# Boris_IO_4.net
KiCad netlist of a schematic drawn in Altium Designer
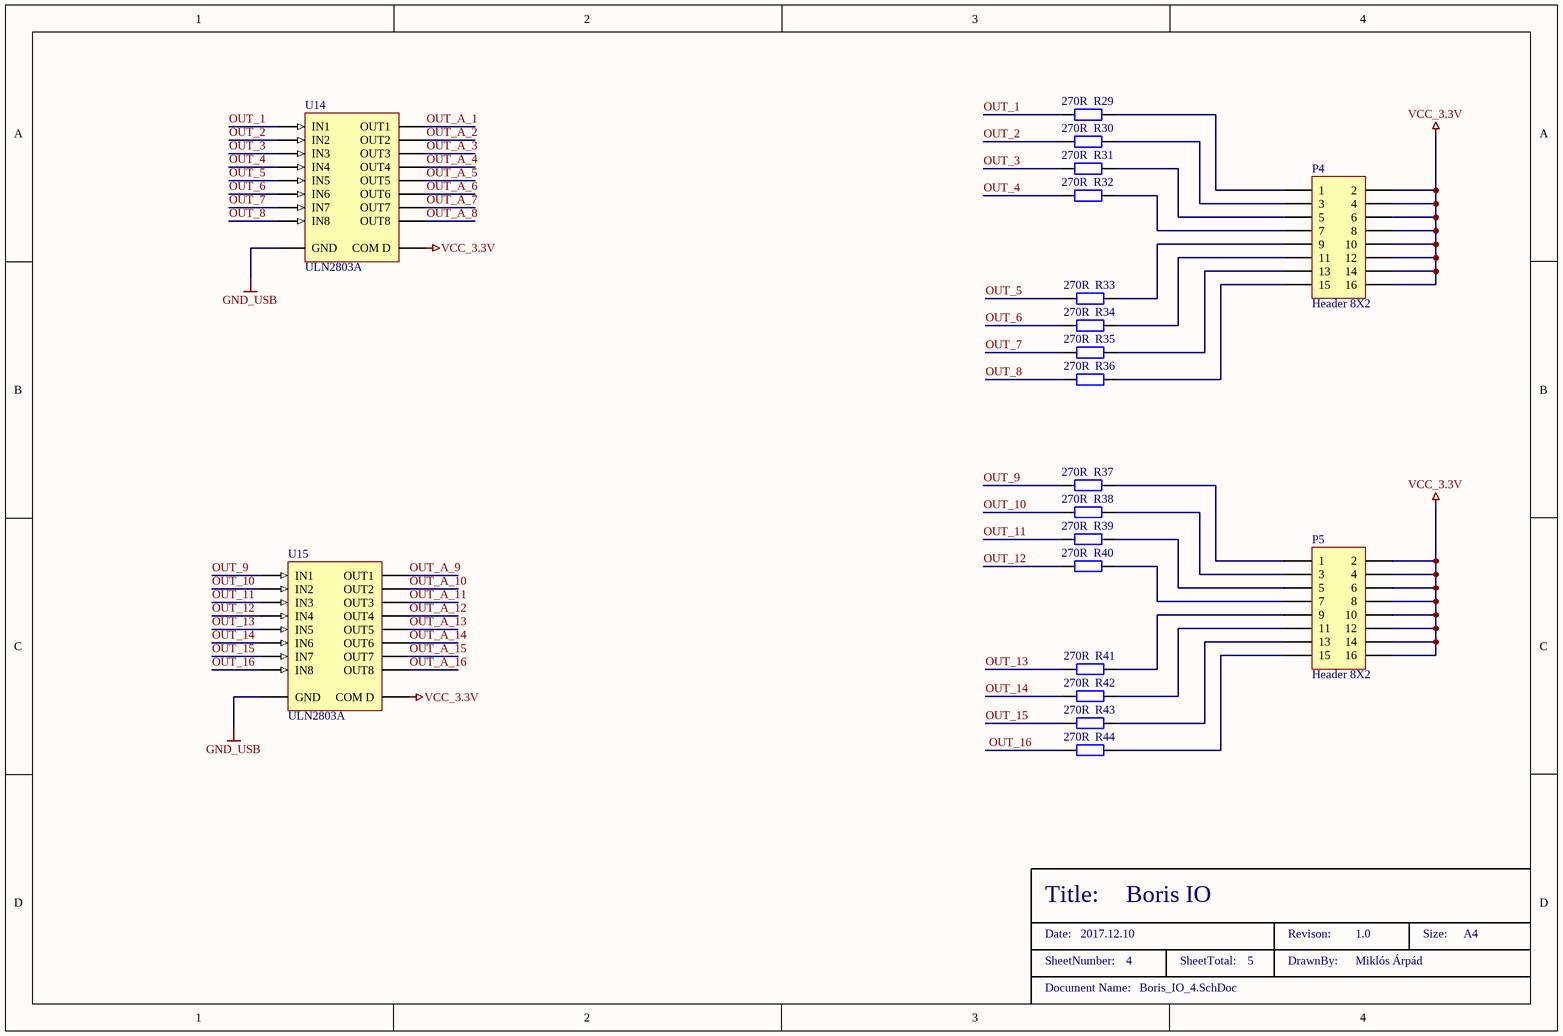
[diagram p0: Boris_IO_4.SchDoc]

(export (version "E")
  (design (tool "Eeschema 10.0.6"))
  (components
    (comp (ref "P4")
      (value "Header 8X2")
      (footprint "HDR2X8")
      (description "Header, 8-Pin, Dual row")
      (fields (field (name "PUBLISHER") "Altium Limited"))
      (libsource (lib "Miscellaneous Connectors") (part "Header 8X2"))
    )
    (comp (ref "P5")
      (value "Header 8X2")
      (footprint "HDR2X8")
      (description "Header, 8-Pin, Dual row")
      (fields (field (name "PUBLISHER") "Altium Limited"))
      (libsource (lib "Miscellaneous Connectors") (part "Header 8X2"))
    )
    (comp (ref "R29")
      (value "270R")
      (footprint "0805_RES")
      (description "Resistor")
      (libsource (lib "Miscellaneous Devices") (part "Res2"))
    )
    (comp (ref "R30")
      (value "270R")
      (footprint "0805_RES")
      (description "Resistor")
      (libsource (lib "Miscellaneous Devices") (part "Res2"))
    )
    (comp (ref "R31")
      (value "270R")
      (footprint "0805_RES")
      (description "Resistor")
      (libsource (lib "Miscellaneous Devices") (part "Res2"))
    )
    (comp (ref "R32")
      (value "270R")
      (footprint "0805_RES")
      (description "Resistor")
      (libsource (lib "Miscellaneous Devices") (part "Res2"))
    )
    (comp (ref "R33")
      (value "270R")
      (footprint "0805_RES")
      (description "Resistor")
      (libsource (lib "Miscellaneous Devices") (part "Res2"))
    )
    (comp (ref "R34")
      (value "270R")
      (footprint "0805_RES")
      (description "Resistor")
      (libsource (lib "Miscellaneous Devices") (part "Res2"))
    )
    (comp (ref "R35")
      (value "270R")
      (footprint "0805_RES")
      (description "Resistor")
      (libsource (lib "Miscellaneous Devices") (part "Res2"))
    )
    (comp (ref "R36")
      (value "270R")
      (footprint "0805_RES")
      (description "Resistor")
      (libsource (lib "Miscellaneous Devices") (part "Res2"))
    )
    (comp (ref "R37")
      (value "270R")
      (footprint "0805_RES")
      (description "Resistor")
      (libsource (lib "Miscellaneous Devices") (part "Res2"))
    )
    (comp (ref "R38")
      (value "270R")
      (footprint "0805_RES")
      (description "Resistor")
      (libsource (lib "Miscellaneous Devices") (part "Res2"))
    )
    (comp (ref "R39")
      (value "270R")
      (footprint "0805_RES")
      (description "Resistor")
      (libsource (lib "Miscellaneous Devices") (part "Res2"))
    )
    (comp (ref "R40")
      (value "270R")
      (footprint "0805_RES")
      (description "Resistor")
      (libsource (lib "Miscellaneous Devices") (part "Res2"))
    )
    (comp (ref "R41")
      (value "270R")
      (footprint "0805_RES")
      (description "Resistor")
      (libsource (lib "Miscellaneous Devices") (part "Res2"))
    )
    (comp (ref "R42")
      (value "270R")
      (footprint "0805_RES")
      (description "Resistor")
      (libsource (lib "Miscellaneous Devices") (part "Res2"))
    )
    (comp (ref "R43")
      (value "270R")
      (footprint "0805_RES")
      (description "Resistor")
      (libsource (lib "Miscellaneous Devices") (part "Res2"))
    )
    (comp (ref "R44")
      (value "270R")
      (footprint "0805_RES")
      (description "Resistor")
      (libsource (lib "Miscellaneous Devices") (part "Res2"))
    )
    (comp (ref "U14")
      (value "ULN2803A")
      (footprint "DIP18")
      (description "Eight Darlington Array")
      (fields (field (name "PUBLISHER") "Altium Limited"))
      (libsource (lib "ST Interface Darlington Driver") (part "ULN2803A"))
    )
    (comp (ref "U15")
      (value "ULN2803A")
      (footprint "DIP18")
      (description "Eight Darlington Array")
      (fields (field (name "PUBLISHER") "Altium Limited"))
      (libsource (lib "ST Interface Darlington Driver") (part "ULN2803A"))
    )
  )
  (nets
    (net (code "1") (name "/OUT_1") (class "Default")
      (node (ref "R29") (pin "1") (pinfunction "1_1") (pintype "passive"))
      (node (ref "U14") (pin "1") (pinfunction "IN1_1") (pintype "input"))
    )
    (net (code "2") (name "/OUT_2") (class "Default")
      (node (ref "R30") (pin "1") (pinfunction "1_1") (pintype "passive"))
      (node (ref "U14") (pin "2") (pinfunction "IN2_2") (pintype "input"))
    )
    (net (code "3") (name "/OUT_3") (class "Default")
      (node (ref "R31") (pin "1") (pinfunction "1_1") (pintype "passive"))
      (node (ref "U14") (pin "3") (pinfunction "IN3_3") (pintype "input"))
    )
    (net (code "4") (name "/OUT_4") (class "Default")
      (node (ref "R32") (pin "1") (pinfunction "1_1") (pintype "passive"))
      (node (ref "U14") (pin "4") (pinfunction "IN4_4") (pintype "input"))
    )
    (net (code "5") (name "/OUT_5") (class "Default")
      (node (ref "R33") (pin "1") (pinfunction "1_1") (pintype "passive"))
      (node (ref "U14") (pin "5") (pinfunction "IN5_5") (pintype "input"))
    )
    (net (code "6") (name "/OUT_6") (class "Default")
      (node (ref "R34") (pin "1") (pinfunction "1_1") (pintype "passive"))
      (node (ref "U14") (pin "6") (pinfunction "IN6_6") (pintype "input"))
    )
    (net (code "7") (name "/OUT_7") (class "Default")
      (node (ref "R35") (pin "1") (pinfunction "1_1") (pintype "passive"))
      (node (ref "U14") (pin "7") (pinfunction "IN7_7") (pintype "input"))
    )
    (net (code "8") (name "/OUT_8") (class "Default")
      (node (ref "R36") (pin "1") (pinfunction "1_1") (pintype "passive"))
      (node (ref "U14") (pin "8") (pinfunction "IN8_8") (pintype "input"))
    )
    (net (code "9") (name "/OUT_9") (class "Default")
      (node (ref "R37") (pin "1") (pinfunction "1_1") (pintype "passive"))
      (node (ref "U15") (pin "1") (pinfunction "IN1_1") (pintype "input"))
    )
    (net (code "10") (name "/OUT_10") (class "Default")
      (node (ref "R38") (pin "1") (pinfunction "1_1") (pintype "passive"))
      (node (ref "U15") (pin "2") (pinfunction "IN2_2") (pintype "input"))
    )
    (net (code "11") (name "/OUT_11") (class "Default")
      (node (ref "R39") (pin "1") (pinfunction "1_1") (pintype "passive"))
      (node (ref "U15") (pin "3") (pinfunction "IN3_3") (pintype "input"))
    )
    (net (code "12") (name "/OUT_12") (class "Default")
      (node (ref "R40") (pin "1") (pinfunction "1_1") (pintype "passive"))
      (node (ref "U15") (pin "4") (pinfunction "IN4_4") (pintype "input"))
    )
    (net (code "13") (name "/OUT_13") (class "Default")
      (node (ref "R41") (pin "1") (pinfunction "1_1") (pintype "passive"))
      (node (ref "U15") (pin "5") (pinfunction "IN5_5") (pintype "input"))
    )
    (net (code "14") (name "/OUT_14") (class "Default")
      (node (ref "R42") (pin "1") (pinfunction "1_1") (pintype "passive"))
      (node (ref "U15") (pin "6") (pinfunction "IN6_6") (pintype "input"))
    )
    (net (code "15") (name "/OUT_15") (class "Default")
      (node (ref "R43") (pin "1") (pinfunction "1_1") (pintype "passive"))
      (node (ref "U15") (pin "7") (pinfunction "IN7_7") (pintype "input"))
    )
    (net (code "16") (name "/OUT_16") (class "Default")
      (node (ref "R44") (pin "1") (pinfunction "1_1") (pintype "passive"))
      (node (ref "U15") (pin "8") (pinfunction "IN8_8") (pintype "input"))
    )
    (net (code "17") (name "/OUT_A_1") (class "Default")
      (node (ref "U14") (pin "18") (pinfunction "OUT1_18") (pintype "open_collector"))
    )
    (net (code "18") (name "/OUT_A_2") (class "Default")
      (node (ref "U14") (pin "17") (pinfunction "OUT2_17") (pintype "open_collector"))
    )
    (net (code "19") (name "/OUT_A_3") (class "Default")
      (node (ref "U14") (pin "16") (pinfunction "OUT3_16") (pintype "open_collector"))
    )
    (net (code "20") (name "/OUT_A_4") (class "Default")
      (node (ref "U14") (pin "15") (pinfunction "OUT4_15") (pintype "open_collector"))
    )
    (net (code "21") (name "/OUT_A_5") (class "Default")
      (node (ref "U14") (pin "14") (pinfunction "OUT5_14") (pintype "open_collector"))
    )
    (net (code "22") (name "/OUT_A_6") (class "Default")
      (node (ref "U14") (pin "13") (pinfunction "OUT6_13") (pintype "open_collector"))
    )
    (net (code "23") (name "/OUT_A_7") (class "Default")
      (node (ref "U14") (pin "12") (pinfunction "OUT7_12") (pintype "open_collector"))
    )
    (net (code "24") (name "/OUT_A_8") (class "Default")
      (node (ref "U14") (pin "11") (pinfunction "OUT8_11") (pintype "open_collector"))
    )
    (net (code "25") (name "/OUT_A_9") (class "Default")
      (node (ref "U15") (pin "18") (pinfunction "OUT1_18") (pintype "open_collector"))
    )
    (net (code "26") (name "/OUT_A_10") (class "Default")
      (node (ref "U15") (pin "17") (pinfunction "OUT2_17") (pintype "open_collector"))
    )
    (net (code "27") (name "/OUT_A_11") (class "Default")
      (node (ref "U15") (pin "16") (pinfunction "OUT3_16") (pintype "open_collector"))
    )
    (net (code "28") (name "/OUT_A_12") (class "Default")
      (node (ref "U15") (pin "15") (pinfunction "OUT4_15") (pintype "open_collector"))
    )
    (net (code "29") (name "/OUT_A_13") (class "Default")
      (node (ref "U15") (pin "14") (pinfunction "OUT5_14") (pintype "open_collector"))
    )
    (net (code "30") (name "/OUT_A_14") (class "Default")
      (node (ref "U15") (pin "13") (pinfunction "OUT6_13") (pintype "open_collector"))
    )
    (net (code "31") (name "/OUT_A_15") (class "Default")
      (node (ref "U15") (pin "12") (pinfunction "OUT7_12") (pintype "open_collector"))
    )
    (net (code "32") (name "/OUT_A_16") (class "Default")
      (node (ref "U15") (pin "11") (pinfunction "OUT8_11") (pintype "open_collector"))
    )
    (net (code "33") (name "GND_USB") (class "Default")
      (node (ref "U14") (pin "9") (pinfunction "GND_9") (pintype "power_in"))
      (node (ref "U15") (pin "9") (pinfunction "GND_9") (pintype "power_in"))
    )
    (net (code "34") (name "Net-(P4-Pad1)") (class "Default")
      (node (ref "P4") (pin "1") (pinfunction "1_1") (pintype "passive"))
      (node (ref "R29") (pin "2") (pinfunction "2_2") (pintype "passive"))
    )
    (net (code "35") (name "Net-(P4-Pad3)") (class "Default")
      (node (ref "P4") (pin "3") (pinfunction "3_3") (pintype "passive"))
      (node (ref "R30") (pin "2") (pinfunction "2_2") (pintype "passive"))
    )
    (net (code "36") (name "Net-(P4-Pad5)") (class "Default")
      (node (ref "P4") (pin "5") (pinfunction "5_5") (pintype "passive"))
      (node (ref "R31") (pin "2") (pinfunction "2_2") (pintype "passive"))
    )
    (net (code "37") (name "Net-(P4-Pad7)") (class "Default")
      (node (ref "P4") (pin "7") (pinfunction "7_7") (pintype "passive"))
      (node (ref "R32") (pin "2") (pinfunction "2_2") (pintype "passive"))
    )
    (net (code "38") (name "Net-(P4-Pad9)") (class "Default")
      (node (ref "P4") (pin "9") (pinfunction "9_9") (pintype "passive"))
      (node (ref "R33") (pin "2") (pinfunction "2_2") (pintype "passive"))
    )
    (net (code "39") (name "Net-(P4-Pad11)") (class "Default")
      (node (ref "P4") (pin "11") (pinfunction "11_11") (pintype "passive"))
      (node (ref "R34") (pin "2") (pinfunction "2_2") (pintype "passive"))
    )
    (net (code "40") (name "Net-(P4-Pad13)") (class "Default")
      (node (ref "P4") (pin "13") (pinfunction "13_13") (pintype "passive"))
      (node (ref "R35") (pin "2") (pinfunction "2_2") (pintype "passive"))
    )
    (net (code "41") (name "Net-(P4-Pad15)") (class "Default")
      (node (ref "P4") (pin "15") (pinfunction "15_15") (pintype "passive"))
      (node (ref "R36") (pin "2") (pinfunction "2_2") (pintype "passive"))
    )
    (net (code "42") (name "Net-(P5-Pad1)") (class "Default")
      (node (ref "P5") (pin "1") (pinfunction "1_1") (pintype "passive"))
      (node (ref "R37") (pin "2") (pinfunction "2_2") (pintype "passive"))
    )
    (net (code "43") (name "Net-(P5-Pad3)") (class "Default")
      (node (ref "P5") (pin "3") (pinfunction "3_3") (pintype "passive"))
      (node (ref "R38") (pin "2") (pinfunction "2_2") (pintype "passive"))
    )
    (net (code "44") (name "Net-(P5-Pad5)") (class "Default")
      (node (ref "P5") (pin "5") (pinfunction "5_5") (pintype "passive"))
      (node (ref "R39") (pin "2") (pinfunction "2_2") (pintype "passive"))
    )
    (net (code "45") (name "Net-(P5-Pad7)") (class "Default")
      (node (ref "P5") (pin "7") (pinfunction "7_7") (pintype "passive"))
      (node (ref "R40") (pin "2") (pinfunction "2_2") (pintype "passive"))
    )
    (net (code "46") (name "Net-(P5-Pad9)") (class "Default")
      (node (ref "P5") (pin "9") (pinfunction "9_9") (pintype "passive"))
      (node (ref "R41") (pin "2") (pinfunction "2_2") (pintype "passive"))
    )
    (net (code "47") (name "Net-(P5-Pad11)") (class "Default")
      (node (ref "P5") (pin "11") (pinfunction "11_11") (pintype "passive"))
      (node (ref "R42") (pin "2") (pinfunction "2_2") (pintype "passive"))
    )
    (net (code "48") (name "Net-(P5-Pad13)") (class "Default")
      (node (ref "P5") (pin "13") (pinfunction "13_13") (pintype "passive"))
      (node (ref "R43") (pin "2") (pinfunction "2_2") (pintype "passive"))
    )
    (net (code "49") (name "Net-(P5-Pad15)") (class "Default")
      (node (ref "P5") (pin "15") (pinfunction "15_15") (pintype "passive"))
      (node (ref "R44") (pin "2") (pinfunction "2_2") (pintype "passive"))
    )
    (net (code "50") (name "VCC_3.3V") (class "Default")
      (node (ref "P4") (pin "10") (pinfunction "10_10") (pintype "passive"))
      (node (ref "P4") (pin "12") (pinfunction "12_12") (pintype "passive"))
      (node (ref "P4") (pin "14") (pinfunction "14_14") (pintype "passive"))
      (node (ref "P4") (pin "16") (pinfunction "16_16") (pintype "passive"))
      (node (ref "P4") (pin "2") (pinfunction "2_2") (pintype "passive"))
      (node (ref "P4") (pin "4") (pinfunction "4_4") (pintype "passive"))
      (node (ref "P4") (pin "6") (pinfunction "6_6") (pintype "passive"))
      (node (ref "P4") (pin "8") (pinfunction "8_8") (pintype "passive"))
      (node (ref "P5") (pin "10") (pinfunction "10_10") (pintype "passive"))
      (node (ref "P5") (pin "12") (pinfunction "12_12") (pintype "passive"))
      (node (ref "P5") (pin "14") (pinfunction "14_14") (pintype "passive"))
      (node (ref "P5") (pin "16") (pinfunction "16_16") (pintype "passive"))
      (node (ref "P5") (pin "2") (pinfunction "2_2") (pintype "passive"))
      (node (ref "P5") (pin "4") (pinfunction "4_4") (pintype "passive"))
      (node (ref "P5") (pin "6") (pinfunction "6_6") (pintype "passive"))
      (node (ref "P5") (pin "8") (pinfunction "8_8") (pintype "passive"))
      (node (ref "U14") (pin "10") (pinfunction "COM_D_10") (pintype "passive"))
      (node (ref "U15") (pin "10") (pinfunction "COM_D_10") (pintype "passive"))
    )
  )
)
